# Servo-potenciom.net
KiCad netlist of a schematic drawn in EAGLE
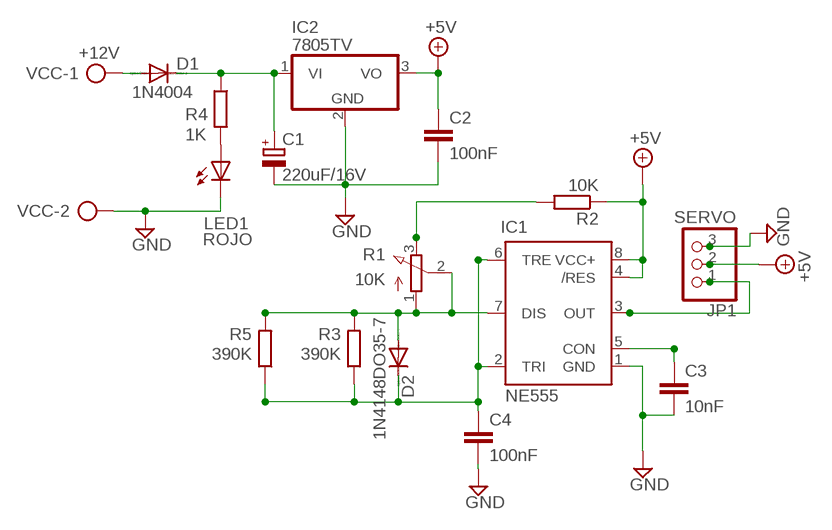
[diagram p0: schematic, sheet 1]

(export (version "E")
  (design (tool "Eeschema 10.0.6"))
  (components
    (comp (ref "C1")
      (value "220uF/16V")
      (footprint "eagle-import:E2,5-7")
      (libsource (lib "eagle-import") (part "CPOL-EUE2.5-7"))
    )
    (comp (ref "C2")
      (value "100nF")
      (footprint "eagle-import:C050-025X075")
      (libsource (lib "eagle-import") (part "C-EU050-025X075"))
    )
    (comp (ref "C3")
      (value "10nF")
      (footprint "eagle-import:C050-025X075")
      (libsource (lib "eagle-import") (part "C-EU050-025X075"))
    )
    (comp (ref "C4")
      (value "100nF")
      (footprint "eagle-import:C050-025X075")
      (libsource (lib "eagle-import") (part "C-EU050-025X075"))
    )
    (comp (ref "D1")
      (value "1N4004")
      (footprint "eagle-import:DO41-10")
      (libsource (lib "eagle-import") (part "1N4004"))
    )
    (comp (ref "D2")
      (value "1N4148DO35-7")
      (footprint "eagle-import:DO35-7")
      (libsource (lib "eagle-import") (part "1N4148DO35-7"))
    )
    (comp (ref "IC1")
      (value "NE555")
      (footprint "eagle-import:DIL-08")
      (fields (field (name "MF") "Arrow Electronics") (field (name "MPN") "NE555N"))
      (libsource (lib "eagle-import") (part "NE555"))
    )
    (comp (ref "IC2")
      (value "7805TV")
      (footprint "eagle-import:TO220V")
      (libsource (lib "eagle-import") (part "78TV05"))
    )
    (comp (ref "JP1")
      (value "SERVO")
      (footprint "eagle-import:1X03")
      (libsource (lib "eagle-import") (part "PINHD-1X3"))
    )
    (comp (ref "LED1")
      (value "ROJO")
      (footprint "eagle-import:LED3MM")
      (libsource (lib "eagle-import") (part "LED3MM"))
    )
    (comp (ref "R1")
      (value "10K")
      (footprint "eagle-import:3RP_1610N")
      (libsource (lib "eagle-import") (part "3RP/1610N"))
    )
    (comp (ref "R2")
      (value "10K")
      (footprint "eagle-import:0207_7")
      (libsource (lib "eagle-import") (part "R-EU_0207/7"))
    )
    (comp (ref "R3")
      (value "390K")
      (footprint "eagle-import:0207_7")
      (libsource (lib "eagle-import") (part "R-EU_0207/7"))
    )
    (comp (ref "R4")
      (value "1K")
      (footprint "eagle-import:0207_7")
      (libsource (lib "eagle-import") (part "R-EU_0207/7"))
    )
    (comp (ref "R5")
      (value "390K")
      (footprint "eagle-import:0207_7")
      (libsource (lib "eagle-import") (part "R-EU_0207/7"))
    )
    (comp (ref "VCC")
      (value "+12V")
      (footprint "eagle-import:AK500_2-H")
      (libsource (lib "eagle-import") (part "AK500/2-H"))
    )
  )
  (nets
    (net (code "1") (name "+5V") (class "Default")
      (node (ref "C2") (pin "1") (pinfunction "1_1") (pintype "passive"))
      (node (ref "IC1") (pin "4") (pinfunction "/RES_4") (pintype "input"))
      (node (ref "IC1") (pin "8") (pinfunction "VCC+_8") (pintype "power_in"))
      (node (ref "IC2") (pin "3") (pinfunction "VO_3") (pintype "passive"))
      (node (ref "JP1") (pin "2") (pinfunction "2_2") (pintype "passive"))
      (node (ref "R2") (pin "1") (pinfunction "1_1") (pintype "passive"))
    )
    (net (code "2") (name "GND") (class "Default")
      (node (ref "C1") (pin "-") (pinfunction "-_-") (pintype "passive"))
      (node (ref "C2") (pin "2") (pinfunction "2_2") (pintype "passive"))
      (node (ref "C3") (pin "2") (pinfunction "2_2") (pintype "passive"))
      (node (ref "C4") (pin "2") (pinfunction "2_2") (pintype "passive"))
      (node (ref "IC1") (pin "1") (pinfunction "GND_1") (pintype "power_in"))
      (node (ref "IC2") (pin "2") (pinfunction "GND_2") (pintype "passive"))
      (node (ref "JP1") (pin "3") (pinfunction "3_3") (pintype "passive"))
      (node (ref "LED1") (pin "K") (pinfunction "C_K") (pintype "passive"))
      (node (ref "VCC") (pin "2") (pinfunction "KL_2") (pintype "passive"))
    )
    (net (code "3") (name "Net-(IC1-CON)") (class "Default")
      (node (ref "C3") (pin "1") (pinfunction "1_1") (pintype "passive"))
      (node (ref "IC1") (pin "5") (pinfunction "CON_5") (pintype "input"))
    )
    (net (code "4") (name "Net-(IC1-DIS)") (class "Default")
      (node (ref "D2") (pin "A") (pinfunction "A_A") (pintype "passive"))
      (node (ref "IC1") (pin "7") (pinfunction "DIS_7") (pintype "input"))
      (node (ref "R1") (pin "1") (pinfunction "A_1") (pintype "passive"))
      (node (ref "R1") (pin "2") (pinfunction "S_2") (pintype "passive"))
      (node (ref "R3") (pin "2") (pinfunction "2_2") (pintype "passive"))
      (node (ref "R5") (pin "2") (pinfunction "2_2") (pintype "passive"))
    )
    (net (code "5") (name "Net-(IC1-OUT)") (class "Default")
      (node (ref "IC1") (pin "3") (pinfunction "OUT_3") (pintype "output"))
      (node (ref "JP1") (pin "1") (pinfunction "1_1") (pintype "passive"))
    )
    (net (code "6") (name "Net-(IC1-TRE)") (class "Default")
      (node (ref "C4") (pin "1") (pinfunction "1_1") (pintype "passive"))
      (node (ref "D2") (pin "C") (pinfunction "C_C") (pintype "passive"))
      (node (ref "IC1") (pin "2") (pinfunction "TRI_2") (pintype "input"))
      (node (ref "IC1") (pin "6") (pinfunction "TRE_6") (pintype "input"))
      (node (ref "R3") (pin "1") (pinfunction "1_1") (pintype "passive"))
      (node (ref "R5") (pin "1") (pinfunction "1_1") (pintype "passive"))
    )
    (net (code "7") (name "Net-(IC2-VI)") (class "Default")
      (node (ref "C1") (pin "+") (pinfunction "+_+") (pintype "passive"))
      (node (ref "D1") (pin "C") (pinfunction "C_C") (pintype "passive"))
      (node (ref "IC2") (pin "1") (pinfunction "VI_1") (pintype "input"))
      (node (ref "R4") (pin "1") (pinfunction "1_1") (pintype "passive"))
    )
    (net (code "8") (name "Net-(LED1-PadA)") (class "Default")
      (node (ref "LED1") (pin "A") (pinfunction "A_A") (pintype "passive"))
      (node (ref "R4") (pin "2") (pinfunction "2_2") (pintype "passive"))
    )
    (net (code "9") (name "Net-(R1-E)") (class "Default")
      (node (ref "R1") (pin "3") (pinfunction "E_3") (pintype "passive"))
      (node (ref "R2") (pin "2") (pinfunction "2_2") (pintype "passive"))
    )
    (net (code "10") (name "Net-(VCCA-KL)") (class "Default")
      (node (ref "D1") (pin "A") (pinfunction "A_A") (pintype "passive"))
      (node (ref "VCC") (pin "1") (pinfunction "KL_1") (pintype "passive"))
    )
  )
)
